# GPS-L86-M33-V0_2.net
KiCad netlist of a schematic drawn in EAGLE
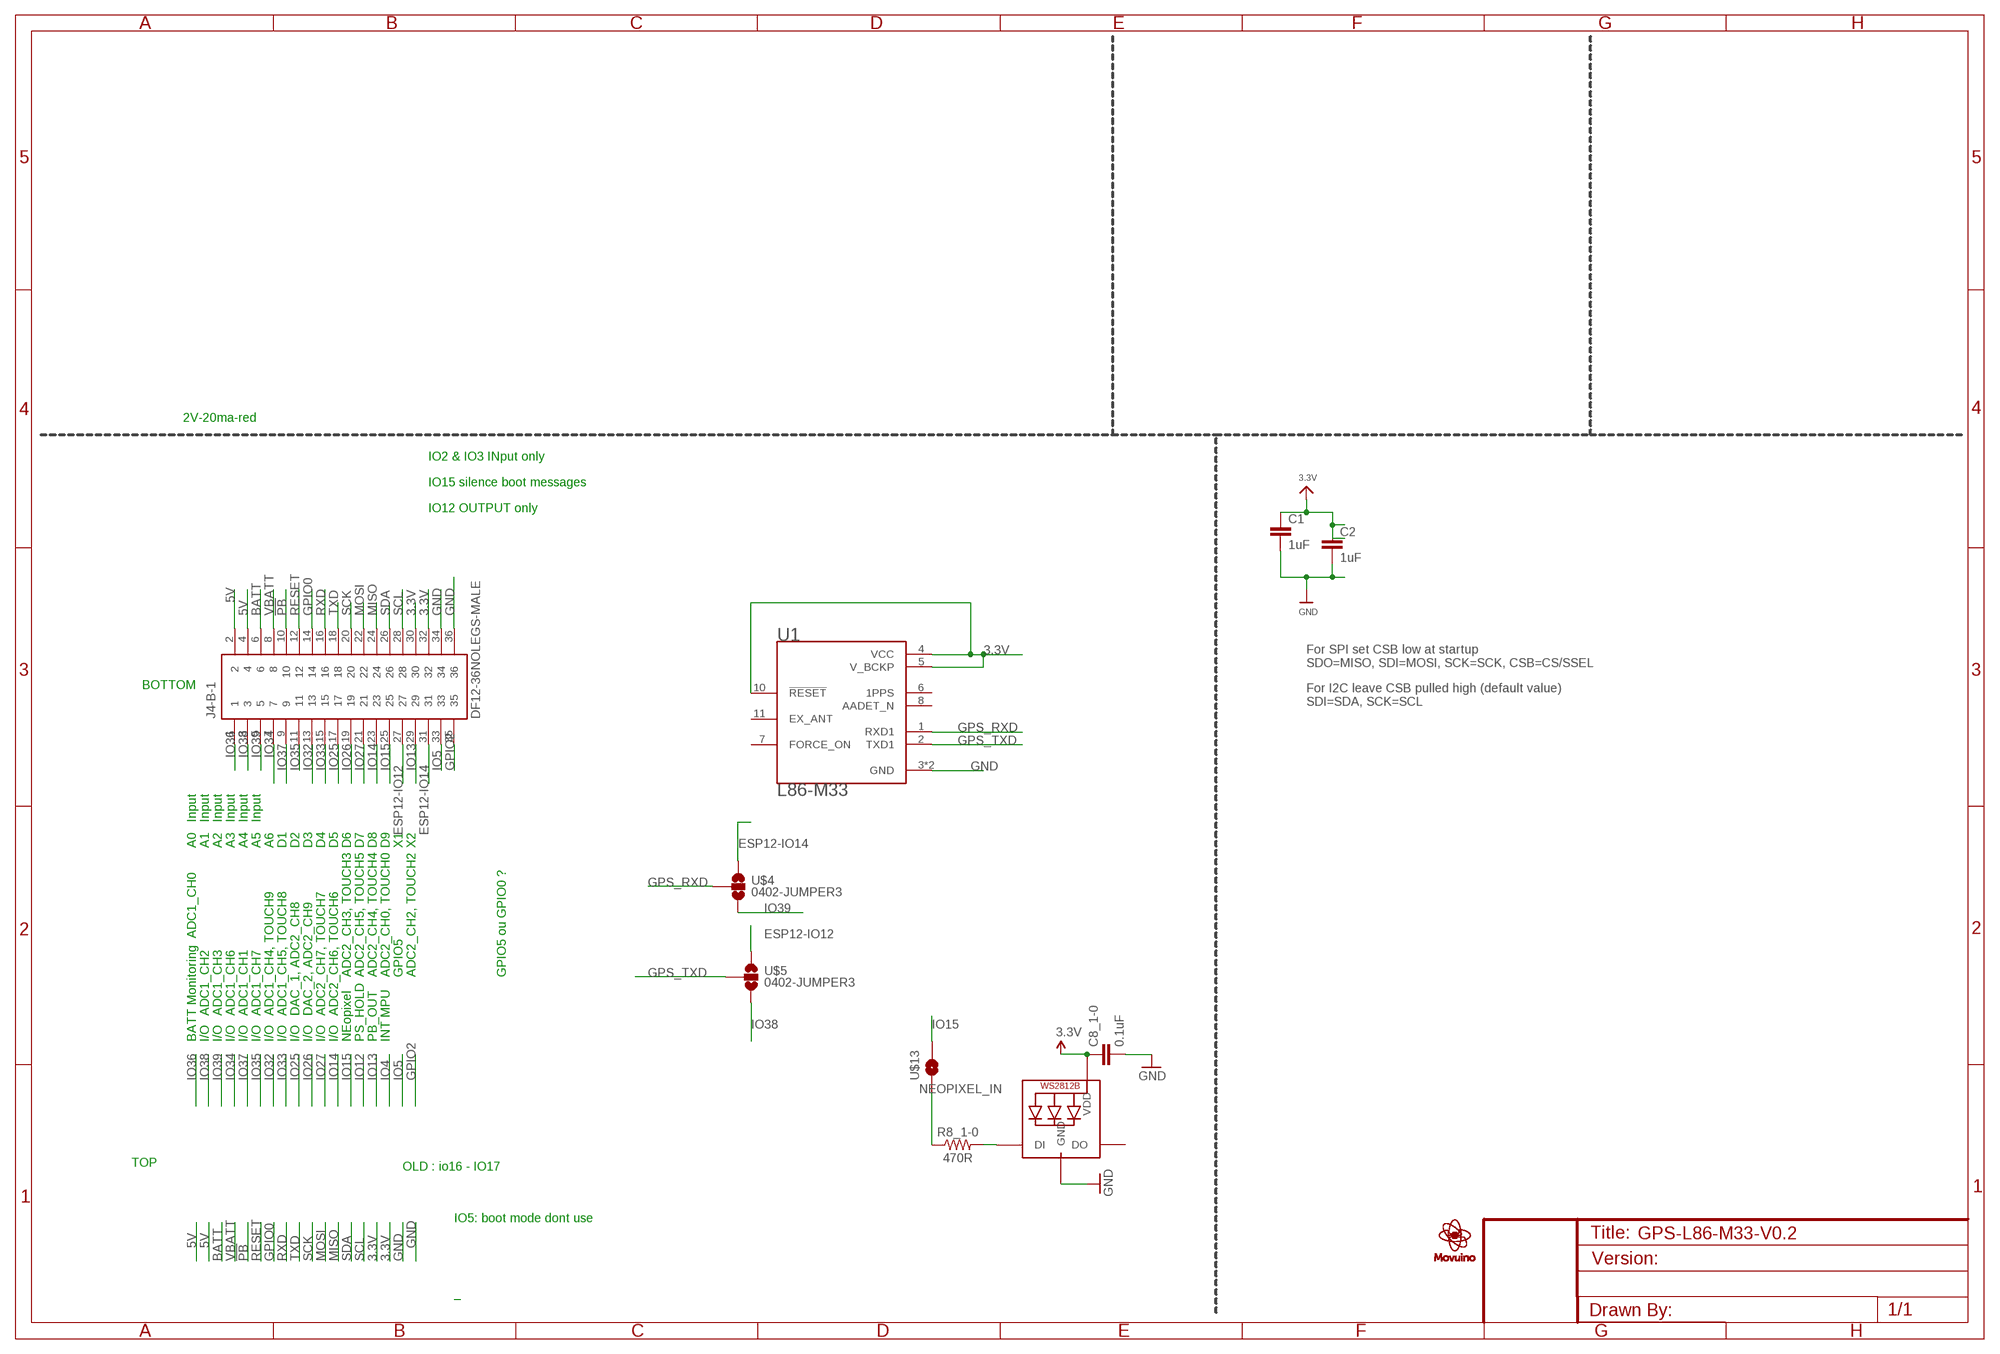
[diagram p0: schematic, sheet 1]

(export (version "E")
  (design (tool "Eeschema 10.0.6"))
  (components
    (comp (ref "C1")
      (value "1uF")
      (footprint "eagle-import:0402-CAP")
      (fields
        (field (name "MF") "Murata Electronics")
        (field (name "MPN") "GRM155R61A105KE15D")
        (field (name "TOLERANCE") "10%")
      )
      (libsource (lib "eagle-import") (part "CAP0402-1UF"))
    )
    (comp (ref "C2")
      (value "1uF")
      (footprint "eagle-import:0402-CAP")
      (fields
        (field (name "MF") "Murata Electronics")
        (field (name "MPN") "GRM155R61A105KE15D")
        (field (name "TOLERANCE") "10%")
      )
      (libsource (lib "eagle-import") (part "CAP0402-1UF"))
    )
    (comp (ref "C8_1-0")
      (value "0.1uF")
      (footprint "eagle-import:0402-CAP")
      (fields
        (field (name "MF") "Murata Electronics")
        (field (name "MPN") "GRM155R61C104KA88D")
        (field (name "TOLERANCE") "10%")
      )
      (libsource (lib "eagle-import") (part "CAP0402-0.1UF"))
    )
    (comp (ref "J4-B-1")
      (value "DF12-36NOLEGS-MALE")
      (footprint "eagle-import:DF12-36-DP-NL")
      (libsource (lib "eagle-import") (part "DF12-36NOLEGS-MALE"))
    )
    (comp (ref "LED1-0")
      (value "WS2812B3535")
      (footprint "eagle-import:LED3535")
      (libsource (lib "eagle-import") (part "WS2812B3535"))
    )
    (comp (ref "R8_1-0")
      (value "470R")
      (footprint "eagle-import:R0402-SMALL-TDOCU")
      (libsource (lib "eagle-import") (part "RESISTORR0402-SMALL-TDOCU"))
    )
    (comp (ref "U$1")
      (value "LOGO_MOVUINOTOP")
      (footprint "eagle-import:LOGO_MOVUINO_BMP_10MM")
      (libsource (lib "eagle-import") (part "LOGO_MOVUINOTOP"))
    )
    (comp (ref "U$4")
      (value "0402-JUMPER3")
      (footprint "eagle-import:SJ_3")
      (libsource (lib "eagle-import") (part "0402-JUMPER3"))
    )
    (comp (ref "U$5")
      (value "0402-JUMPER3")
      (footprint "eagle-import:SJ_3")
      (libsource (lib "eagle-import") (part "0402-JUMPER3"))
    )
    (comp (ref "U$13")
      (value "0402-JUMPERCLOSED-DEFAULT")
      (footprint "eagle-import:0402-JUMPER-CLOSED")
      (libsource (lib "eagle-import") (part "0402-JUMPERCLOSED-DEFAULT"))
    )
    (comp (ref "U1")
      (value "L86-M33")
      (footprint "eagle-import:XCVR_L86-M33")
      (fields (field (name "MF") "Quectel"))
      (libsource (lib "eagle-import") (part "L86-M33"))
    )
  )
  (nets
    (net (code "1") (name "/5V") (class "Default")
      (node (ref "J4-B-1") (pin "2") (pinfunction "2_2") (pintype "bidirectional"))
      (node (ref "J4-B-1") (pin "4") (pinfunction "4_4") (pintype "bidirectional"))
    )
    (net (code "2") (name "/BATT") (class "Default")
      (node (ref "J4-B-1") (pin "6") (pinfunction "6_6") (pintype "bidirectional"))
    )
    (net (code "3") (name "/ESP12-IO12") (class "Default")
      (node (ref "J4-B-1") (pin "27") (pinfunction "27_27") (pintype "bidirectional"))
      (node (ref "U$5") (pin "1") (pinfunction "1_1") (pintype "passive"))
    )
    (net (code "4") (name "/ESP12-IO14") (class "Default")
      (node (ref "J4-B-1") (pin "31") (pinfunction "31_31") (pintype "bidirectional"))
      (node (ref "U$4") (pin "1") (pinfunction "1_1") (pintype "passive"))
    )
    (net (code "5") (name "/GPIO0") (class "Default")
      (node (ref "J4-B-1") (pin "14") (pinfunction "14_14") (pintype "bidirectional"))
    )
    (net (code "6") (name "/GPIO2") (class "Default")
      (node (ref "J4-B-1") (pin "35") (pinfunction "35_35") (pintype "bidirectional"))
    )
    (net (code "7") (name "/GPS_RXD") (class "Default")
      (node (ref "U$4") (pin "2") (pinfunction "2_2") (pintype "passive"))
      (node (ref "U1") (pin "1") (pinfunction "RXD1_1") (pintype "input"))
    )
    (net (code "8") (name "/GPS_TXD") (class "Default")
      (node (ref "U$5") (pin "2") (pinfunction "2_2") (pintype "passive"))
      (node (ref "U1") (pin "2") (pinfunction "TXD1_2") (pintype "output"))
    )
    (net (code "10") (name "/IO5") (class "Default")
      (node (ref "J4-B-1") (pin "33") (pinfunction "33_33") (pintype "bidirectional"))
    )
    (net (code "12") (name "/IO13") (class "Default")
      (node (ref "J4-B-1") (pin "29") (pinfunction "29_29") (pintype "bidirectional"))
    )
    (net (code "13") (name "/IO14") (class "Default")
      (node (ref "J4-B-1") (pin "23") (pinfunction "23_23") (pintype "bidirectional"))
    )
    (net (code "14") (name "/IO15") (class "Default")
      (node (ref "J4-B-1") (pin "25") (pinfunction "25_25") (pintype "bidirectional"))
      (node (ref "U$13") (pin "2") (pinfunction "2_2") (pintype "bidirectional"))
    )
    (net (code "15") (name "/IO25") (class "Default")
      (node (ref "J4-B-1") (pin "17") (pinfunction "17_17") (pintype "bidirectional"))
    )
    (net (code "16") (name "/IO26") (class "Default")
      (node (ref "J4-B-1") (pin "19") (pinfunction "19_19") (pintype "bidirectional"))
    )
    (net (code "17") (name "/IO27") (class "Default")
      (node (ref "J4-B-1") (pin "21") (pinfunction "21_21") (pintype "bidirectional"))
    )
    (net (code "18") (name "/IO32") (class "Default")
      (node (ref "J4-B-1") (pin "13") (pinfunction "13_13") (pintype "bidirectional"))
    )
    (net (code "19") (name "/IO33") (class "Default")
      (node (ref "J4-B-1") (pin "15") (pinfunction "15_15") (pintype "bidirectional"))
    )
    (net (code "20") (name "/IO34") (class "Default")
      (node (ref "J4-B-1") (pin "7") (pinfunction "7_7") (pintype "bidirectional"))
    )
    (net (code "21") (name "/IO35") (class "Default")
      (node (ref "J4-B-1") (pin "11") (pinfunction "11_11") (pintype "bidirectional"))
    )
    (net (code "22") (name "/IO36") (class "Default")
      (node (ref "J4-B-1") (pin "1") (pinfunction "1_1") (pintype "bidirectional"))
    )
    (net (code "23") (name "/IO37") (class "Default")
      (node (ref "J4-B-1") (pin "9") (pinfunction "9_9") (pintype "bidirectional"))
    )
    (net (code "24") (name "/IO38") (class "Default")
      (node (ref "J4-B-1") (pin "3") (pinfunction "3_3") (pintype "bidirectional"))
      (node (ref "U$5") (pin "3") (pinfunction "3_3") (pintype "passive"))
    )
    (net (code "25") (name "/IO39") (class "Default")
      (node (ref "J4-B-1") (pin "5") (pinfunction "5_5") (pintype "bidirectional"))
      (node (ref "U$4") (pin "3") (pinfunction "3_3") (pintype "passive"))
    )
    (net (code "26") (name "/MISO") (class "Default")
      (node (ref "J4-B-1") (pin "24") (pinfunction "24_24") (pintype "bidirectional"))
    )
    (net (code "27") (name "/MOSI") (class "Default")
      (node (ref "J4-B-1") (pin "22") (pinfunction "22_22") (pintype "bidirectional"))
    )
    (net (code "28") (name "/NEOPIXEL_IN") (class "Default")
      (node (ref "R8_1-0") (pin "1") (pinfunction "1_1") (pintype "passive"))
      (node (ref "U$13") (pin "1") (pinfunction "1_1") (pintype "bidirectional"))
    )
    (net (code "29") (name "/RESET") (class "Default")
      (node (ref "J4-B-1") (pin "12") (pinfunction "12_12") (pintype "bidirectional"))
    )
    (net (code "30") (name "/RXD") (class "Default")
      (node (ref "J4-B-1") (pin "16") (pinfunction "16_16") (pintype "bidirectional"))
    )
    (net (code "31") (name "/SCK") (class "Default")
      (node (ref "J4-B-1") (pin "20") (pinfunction "20_20") (pintype "bidirectional"))
    )
    (net (code "32") (name "/SCL") (class "Default")
      (node (ref "J4-B-1") (pin "28") (pinfunction "28_28") (pintype "bidirectional"))
    )
    (net (code "33") (name "/SDA") (class "Default")
      (node (ref "J4-B-1") (pin "26") (pinfunction "26_26") (pintype "bidirectional"))
    )
    (net (code "34") (name "/TXD") (class "Default")
      (node (ref "J4-B-1") (pin "18") (pinfunction "18_18") (pintype "bidirectional"))
    )
    (net (code "35") (name "/VBATT") (class "Default")
      (node (ref "J4-B-1") (pin "8") (pinfunction "8_8") (pintype "bidirectional"))
    )
    (net (code "36") (name "/~{PB}") (class "Default")
      (node (ref "J4-B-1") (pin "10") (pinfunction "10_10") (pintype "bidirectional"))
    )
    (net (code "37") (name "3.3V") (class "Default")
      (node (ref "C1") (pin "1") (pinfunction "1_1") (pintype "passive"))
      (node (ref "C2") (pin "1") (pinfunction "1_1") (pintype "passive"))
      (node (ref "C8_1-0") (pin "1") (pinfunction "1_1") (pintype "passive"))
      (node (ref "J4-B-1") (pin "30") (pinfunction "30_30") (pintype "bidirectional"))
      (node (ref "J4-B-1") (pin "32") (pinfunction "32_32") (pintype "bidirectional"))
      (node (ref "LED1-0") (pin "2") (pinfunction "VDD_2") (pintype "power_in"))
      (node (ref "U1") (pin "10") (pinfunction "~{RESET}_10") (pintype "input"))
      (node (ref "U1") (pin "4") (pinfunction "VCC_4") (pintype "power_in"))
      (node (ref "U1") (pin "5") (pinfunction "V_BCKP_5") (pintype "power_in"))
    )
    (net (code "38") (name "GND") (class "Default")
      (node (ref "C1") (pin "2") (pinfunction "2_2") (pintype "passive"))
      (node (ref "C2") (pin "2") (pinfunction "2_2") (pintype "passive"))
      (node (ref "C8_1-0") (pin "2") (pinfunction "2_2") (pintype "passive"))
      (node (ref "J4-B-1") (pin "34") (pinfunction "34_34") (pintype "bidirectional"))
      (node (ref "J4-B-1") (pin "36") (pinfunction "36_36") (pintype "bidirectional"))
      (node (ref "LED1-0") (pin "4") (pinfunction "GND_4") (pintype "power_in"))
      (node (ref "U1") (pin "12") (pinfunction "GND_12") (pintype "passive"))
      (node (ref "U1") (pin "3") (pinfunction "GND_3") (pintype "passive"))
    )
    (net (code "39") (name "Net-(LED1-0-DI)") (class "Default")
      (node (ref "LED1-0") (pin "1") (pinfunction "DI_1") (pintype "input"))
      (node (ref "R8_1-0") (pin "2") (pinfunction "2_2") (pintype "passive"))
    )
    (net (code "40") (name "unconnected-(LED1-0-DO-Pad3)") (class "Default")
      (node (ref "LED1-0") (pin "3") (pinfunction "DO_3") (pintype "output"))
    )
    (net (code "41") (name "unconnected-(U1-1PPS-Pad6)") (class "Default")
      (node (ref "U1") (pin "6") (pinfunction "1PPS_6") (pintype "output"))
    )
    (net (code "42") (name "unconnected-(U1-AADET_N-Pad8)") (class "Default")
      (node (ref "U1") (pin "8") (pinfunction "AADET_N_8") (pintype "output"))
    )
    (net (code "43") (name "unconnected-(U1-EX_ANT-Pad11)") (class "Default")
      (node (ref "U1") (pin "11") (pinfunction "EX_ANT_11") (pintype "input"))
    )
    (net (code "44") (name "unconnected-(U1-FORCE_ON-Pad7)") (class "Default")
      (node (ref "U1") (pin "7") (pinfunction "FORCE_ON_7") (pintype "input"))
    )
  )
)
